# RS485.net
KiCad netlist of a schematic drawn in Altium Designer
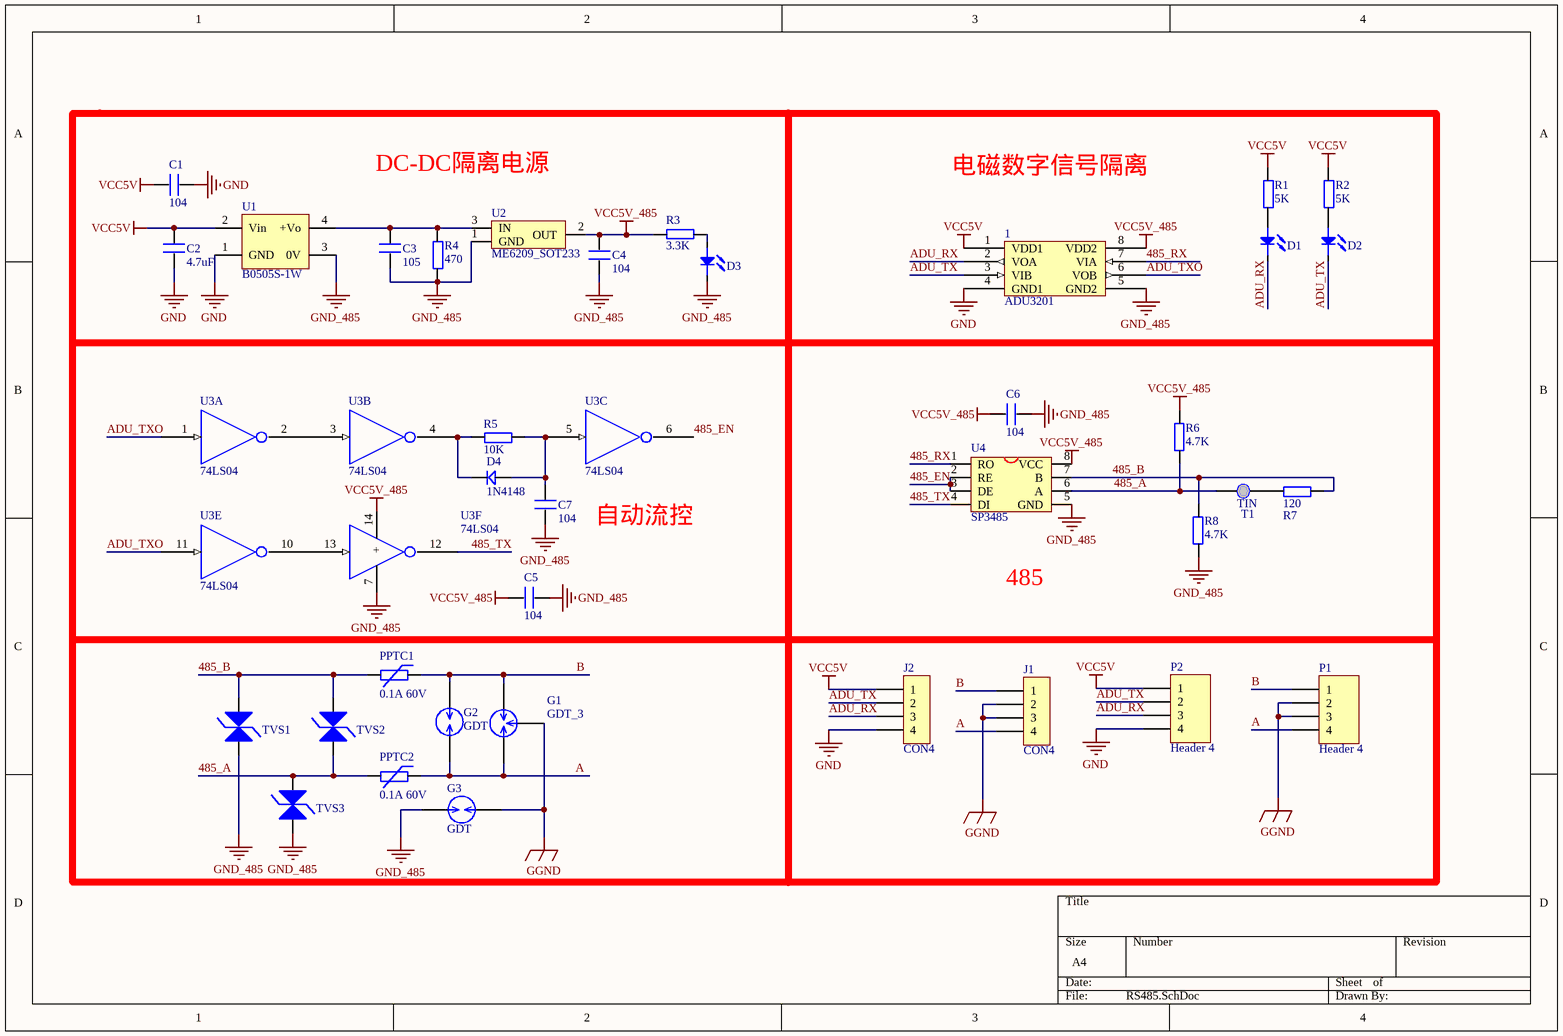
[diagram p0: RS485.SchDoc]

(export (version "E")
  (design (tool "Eeschema 10.0.6"))
  (components
    (comp (ref "1") (value "ADU3201") (footprint "SO-8") (libsource (lib "Mylib") (part "ADU3201")))
    (comp (ref "C1") (value "104") (footprint "C_0805") (libsource (lib "Mylib") (part "C")))
    (comp (ref "C2") (value "4.7uF") (footprint "C_0805") (libsource (lib "Mylib") (part "C")))
    (comp (ref "C3") (value "105") (footprint "C_0805") (libsource (lib "Mylib") (part "C")))
    (comp (ref "C4") (value "104") (footprint "C_0805") (libsource (lib "Mylib") (part "C")))
    (comp (ref "C5") (value "104") (footprint "C_0805") (libsource (lib "Mylib") (part "C")))
    (comp (ref "C6") (value "104") (footprint "C_0805") (libsource (lib "Mylib") (part "C")))
    (comp (ref "C7") (value "104") (footprint "C_0805") (libsource (lib "Mylib") (part "C")))
    (comp (ref "D1") (value "LED") (footprint "0805-LED-RED") (libsource (lib "MY SCH LIB") (part "LED")))
    (comp (ref "D2") (value "LED") (footprint "0805-LED-RED") (libsource (lib "MY SCH LIB") (part "LED")))
    (comp (ref "D3") (value "LED") (footprint "0805-LED-RED") (libsource (lib "MY SCH LIB") (part "LED")))
    (comp (ref "D4") (value "1N4148") (footprint "DIODE-1206") (libsource (lib "Mylib") (part "D")))
    (comp (ref "G1")
      (value "GDT_3")
      (footprint "GDT3B")
      (description "放电器")
      (libsource (lib "Mylib") (part "GDT_3"))
    )
    (comp (ref "G2")
      (value "GDT")
      (footprint "1812_C")
      (description "放电器")
      (libsource (lib "Mylib") (part "GDT"))
    )
    (comp (ref "G3")
      (value "GDT")
      (footprint "1812_C")
      (description "放电器")
      (libsource (lib "Mylib") (part "GDT"))
    )
    (comp (ref "J1") (value "CON4") (footprint "Conect4_3.81E") (libsource (lib "接口插座") (part "CON4")))
    (comp (ref "J2") (value "CON4") (footprint "Conect4_3.81E") (libsource (lib "接口插座") (part "CON4")))
    (comp (ref "P1")
      (value "Header 4")
      (footprint "HDR1X4")
      (description "Header, 4-Pin")
      (fields (field (name "PUBLISHER") "Altium Limited"))
      (libsource (lib "接口插座") (part "Header 4"))
    )
    (comp (ref "P2")
      (value "Header 4")
      (footprint "HDR1X4")
      (description "Header, 4-Pin")
      (fields (field (name "PUBLISHER") "Altium Limited"))
      (libsource (lib "接口插座") (part "Header 4"))
    )
    (comp (ref "PPTC1") (value "0.1A 60V") (footprint "1812F") (libsource (lib "Mylib") (part "PPTC")))
    (comp (ref "PPTC2") (value "0.1A 60V") (footprint "1812F") (libsource (lib "Mylib") (part "PPTC")))
    (comp (ref "R1") (value "5K") (footprint "0805") (libsource (lib "Mylib") (part "R")))
    (comp (ref "R2") (value "5K") (footprint "0805") (libsource (lib "Mylib") (part "R")))
    (comp (ref "R3") (value "3.3K") (footprint "0805") (libsource (lib "Mylib") (part "R")))
    (comp (ref "R4") (value "470") (footprint "0805") (libsource (lib "Mylib") (part "R")))
    (comp (ref "R5") (value "10K") (footprint "0805") (libsource (lib "Mylib") (part "R")))
    (comp (ref "R6") (value "4.7K") (footprint "0805") (libsource (lib "Mylib") (part "R")))
    (comp (ref "R7") (value "120") (footprint "0805") (libsource (lib "Mylib") (part "R")))
    (comp (ref "R8") (value "4.7K") (footprint "0805") (libsource (lib "Mylib") (part "R")))
    (comp (ref "T1") (value "TIN") (footprint "TIN") (libsource (lib "Mylib") (part "TIN")))
    (comp (ref "TVS1")
      (value "TVS_2")
      (footprint "DIODE-SMA")
      (description "TVS双向二极管")
      (fields (field (name "PUBLISHER") "Altium Limited"))
      (libsource (lib "Mylib") (part "TVS_2"))
    )
    (comp (ref "TVS2")
      (value "TVS_2")
      (footprint "DIODE-SMA")
      (description "TVS双向二极管")
      (fields (field (name "PUBLISHER") "Altium Limited"))
      (libsource (lib "Mylib") (part "TVS_2"))
    )
    (comp (ref "TVS3")
      (value "TVS_2")
      (footprint "DIODE-SMA")
      (description "TVS双向二极管")
      (fields (field (name "PUBLISHER") "Altium Limited"))
      (libsource (lib "Mylib") (part "TVS_2"))
    )
    (comp (ref "U1")
      (value "B0505S-1W")
      (footprint "B0505S-1W")
      (description "DC/DC隔离电源（Mornsun）")
      (libsource (lib "Mylib") (part "B0505S-1W"))
    )
    (comp (ref "U2")
      (value "ME6209_SOT233")
      (footprint "SOT-23 - duplicate1")
      (libsource (lib "Mylib") (part "ME6209"))
    )
    (comp (ref "U3")
      (value "74LS04")
      (footprint "SOP-14N")
      (description "非门")
      (libsource (lib "SMC_Devices") (part "74LS04"))
    )
    (comp (ref "U4")
      (value "SP3485")
      (footprint "SOP-8")
      (libsource (lib "战舰STM32开发板底板封装库") (part "MAX3485"))
    )
  )
  (nets
    (net (code "1") (name "/485_A") (class "Default")
      (node (ref "PPTC2") (pin "1") (pintype "passive"))
      (node (ref "R6") (pin "2") (pintype "passive"))
      (node (ref "T1") (pin "2") (pinfunction "2_2") (pintype "passive"))
      (node (ref "TVS2") (pin "1") (pinfunction "A_1") (pintype "passive"))
      (node (ref "TVS3") (pin "1") (pinfunction "A_1") (pintype "passive"))
      (node (ref "U4") (pin "6") (pinfunction "A_6") (pintype "passive"))
    )
    (net (code "2") (name "/485_B") (class "Default")
      (node (ref "PPTC1") (pin "1") (pintype "passive"))
      (node (ref "R7") (pin "2") (pintype "passive"))
      (node (ref "R8") (pin "1") (pintype "passive"))
      (node (ref "TVS1") (pin "2") (pinfunction "K_2") (pintype "passive"))
      (node (ref "TVS2") (pin "2") (pinfunction "K_2") (pintype "passive"))
      (node (ref "U4") (pin "7") (pinfunction "B_7") (pintype "passive"))
    )
    (net (code "3") (name "/485_EN") (class "Default")
      (node (ref "U3") (pin "6") (pinfunction "6_6") (pintype "passive"))
      (node (ref "U4") (pin "2") (pinfunction "RE_2") (pintype "passive"))
      (node (ref "U4") (pin "3") (pinfunction "DE_3") (pintype "passive"))
    )
    (net (code "4") (name "/485_RX") (class "Default")
      (node (ref "1") (pin "7") (pinfunction "VIA_7") (pintype "input"))
      (node (ref "U4") (pin "1") (pinfunction "RO_1") (pintype "passive"))
    )
    (net (code "5") (name "/485_TX") (class "Default")
      (node (ref "U3") (pin "12") (pinfunction "12_12") (pintype "passive"))
      (node (ref "U4") (pin "4") (pinfunction "DI_4") (pintype "passive"))
    )
    (net (code "6") (name "/A") (class "Default")
      (node (ref "G1") (pin "3") (pinfunction "3_3") (pintype "passive"))
      (node (ref "G2") (pin "1") (pinfunction "1_1") (pintype "passive"))
      (node (ref "J1") (pin "4") (pinfunction "4_4") (pintype "passive"))
      (node (ref "P1") (pin "4") (pinfunction "4_4") (pintype "passive"))
      (node (ref "PPTC2") (pin "2") (pintype "passive"))
    )
    (net (code "7") (name "/ADU_RX") (class "Default")
      (node (ref "1") (pin "2") (pinfunction "VOA_2") (pintype "output"))
      (node (ref "D1") (pin "K") (pintype "passive"))
      (node (ref "J2") (pin "3") (pinfunction "3_3") (pintype "passive"))
      (node (ref "P2") (pin "3") (pinfunction "3_3") (pintype "passive"))
    )
    (net (code "8") (name "/ADU_TX") (class "Default")
      (node (ref "1") (pin "3") (pinfunction "VIB_3") (pintype "input"))
      (node (ref "D2") (pin "K") (pintype "passive"))
      (node (ref "J2") (pin "2") (pinfunction "2_2") (pintype "passive"))
      (node (ref "P2") (pin "2") (pinfunction "2_2") (pintype "passive"))
    )
    (net (code "9") (name "/ADU_TXO") (class "Default")
      (node (ref "1") (pin "6") (pinfunction "VOB_6") (pintype "output"))
      (node (ref "U3") (pin "1") (pinfunction "1_1") (pintype "input"))
      (node (ref "U3") (pin "11") (pinfunction "11_11") (pintype "input"))
    )
    (net (code "10") (name "/B") (class "Default")
      (node (ref "G1") (pin "1") (pinfunction "1_1") (pintype "passive"))
      (node (ref "G2") (pin "2") (pinfunction "2_2") (pintype "passive"))
      (node (ref "J1") (pin "1") (pinfunction "1_1") (pintype "passive"))
      (node (ref "P1") (pin "1") (pinfunction "1_1") (pintype "passive"))
      (node (ref "PPTC1") (pin "2") (pintype "passive"))
    )
    (net (code "11") (name "GGND") (class "Default")
      (node (ref "G1") (pin "2") (pinfunction "2_2") (pintype "passive"))
      (node (ref "G3") (pin "2") (pinfunction "2_2") (pintype "passive"))
      (node (ref "J1") (pin "2") (pinfunction "2_2") (pintype "passive"))
      (node (ref "J1") (pin "3") (pinfunction "3_3") (pintype "passive"))
      (node (ref "P1") (pin "2") (pinfunction "2_2") (pintype "passive"))
      (node (ref "P1") (pin "3") (pinfunction "3_3") (pintype "passive"))
    )
    (net (code "12") (name "GND") (class "Default")
      (node (ref "1") (pin "4") (pinfunction "GND1_4") (pintype "power_in"))
      (node (ref "C1") (pin "1") (pintype "passive"))
      (node (ref "C2") (pin "1") (pintype "passive"))
      (node (ref "J2") (pin "4") (pinfunction "4_4") (pintype "passive"))
      (node (ref "P2") (pin "4") (pinfunction "4_4") (pintype "passive"))
      (node (ref "U1") (pin "1") (pinfunction "GND_1") (pintype "passive"))
    )
    (net (code "13") (name "GND_485") (class "Default")
      (node (ref "1") (pin "5") (pinfunction "GND2_5") (pintype "power_in"))
      (node (ref "C3") (pin "1") (pintype "passive"))
      (node (ref "C4") (pin "1") (pintype "passive"))
      (node (ref "C5") (pin "1") (pintype "passive"))
      (node (ref "C6") (pin "1") (pintype "passive"))
      (node (ref "C7") (pin "2") (pintype "passive"))
      (node (ref "D3") (pin "K") (pintype "passive"))
      (node (ref "G3") (pin "1") (pinfunction "1_1") (pintype "passive"))
      (node (ref "R4") (pin "1") (pintype "passive"))
      (node (ref "R8") (pin "2") (pintype "passive"))
      (node (ref "TVS1") (pin "1") (pinfunction "A_1") (pintype "passive"))
      (node (ref "TVS3") (pin "2") (pinfunction "K_2") (pintype "passive"))
      (node (ref "U1") (pin "3") (pinfunction "0V_3") (pintype "passive"))
      (node (ref "U2") (pin "1") (pinfunction "GND_1") (pintype "passive"))
      (node (ref "U3") (pin "7") (pinfunction "7_7") (pintype "passive"))
      (node (ref "U4") (pin "5") (pinfunction "GND_5") (pintype "passive"))
    )
    (net (code "14") (name "Net-(C7-Pad1)") (class "Default")
      (node (ref "C7") (pin "1") (pintype "passive"))
      (node (ref "D4") (pin "1") (pintype "passive"))
      (node (ref "R5") (pin "2") (pintype "passive"))
      (node (ref "U3") (pin "5") (pinfunction "5_5") (pintype "input"))
    )
    (net (code "15") (name "Net-(D1-PadA)") (class "Default")
      (node (ref "D1") (pin "A") (pintype "passive"))
      (node (ref "R1") (pin "1") (pintype "passive"))
    )
    (net (code "16") (name "Net-(D2-PadA)") (class "Default")
      (node (ref "D2") (pin "A") (pintype "passive"))
      (node (ref "R2") (pin "1") (pintype "passive"))
    )
    (net (code "17") (name "Net-(D3-PadA)") (class "Default")
      (node (ref "D3") (pin "A") (pintype "passive"))
      (node (ref "R3") (pin "1") (pintype "passive"))
    )
    (net (code "18") (name "Net-(D4-Pad2)") (class "Default")
      (node (ref "D4") (pin "2") (pintype "passive"))
      (node (ref "R5") (pin "1") (pintype "passive"))
      (node (ref "U3") (pin "4") (pinfunction "4_4") (pintype "passive"))
    )
    (net (code "19") (name "Net-(R7-Pad1)") (class "Default")
      (node (ref "R7") (pin "1") (pintype "passive"))
      (node (ref "T1") (pin "1") (pinfunction "1_1") (pintype "passive"))
    )
    (net (code "20") (name "Net-(U1-+Vo)") (class "Default")
      (node (ref "C3") (pin "2") (pintype "passive"))
      (node (ref "R4") (pin "2") (pintype "passive"))
      (node (ref "U1") (pin "4") (pinfunction "+Vo_4") (pintype "passive"))
      (node (ref "U2") (pin "3") (pinfunction "IN_3") (pintype "passive"))
    )
    (net (code "21") (name "Net-(U3-Pad2)") (class "Default")
      (node (ref "U3") (pin "2") (pinfunction "2_2") (pintype "passive"))
      (node (ref "U3") (pin "3") (pinfunction "3_3") (pintype "input"))
    )
    (net (code "22") (name "Net-(U3-Pad10)") (class "Default")
      (node (ref "U3") (pin "10") (pinfunction "10_10") (pintype "passive"))
      (node (ref "U3") (pin "13") (pinfunction "13_13") (pintype "input"))
    )
    (net (code "23") (name "VCC5V") (class "Default")
      (node (ref "1") (pin "1") (pinfunction "VDD1_1") (pintype "power_in"))
      (node (ref "C1") (pin "2") (pintype "passive"))
      (node (ref "C2") (pin "2") (pintype "passive"))
      (node (ref "J2") (pin "1") (pinfunction "1_1") (pintype "passive"))
      (node (ref "P2") (pin "1") (pinfunction "1_1") (pintype "passive"))
      (node (ref "R1") (pin "2") (pintype "passive"))
      (node (ref "R2") (pin "2") (pintype "passive"))
      (node (ref "U1") (pin "2") (pinfunction "Vin_2") (pintype "passive"))
    )
    (net (code "24") (name "VCC5V_485") (class "Default")
      (node (ref "1") (pin "8") (pinfunction "VDD2_8") (pintype "power_in"))
      (node (ref "C4") (pin "2") (pintype "passive"))
      (node (ref "C5") (pin "2") (pintype "passive"))
      (node (ref "C6") (pin "2") (pintype "passive"))
      (node (ref "R3") (pin "2") (pintype "passive"))
      (node (ref "R6") (pin "1") (pintype "passive"))
      (node (ref "U2") (pin "2") (pinfunction "OUT_2") (pintype "passive"))
      (node (ref "U3") (pin "14") (pinfunction "+_14") (pintype "passive"))
      (node (ref "U4") (pin "8") (pinfunction "VCC_8") (pintype "passive"))
    )
  )
)
